# USB_UART.net
KiCad netlist of a schematic drawn in Altium Designer
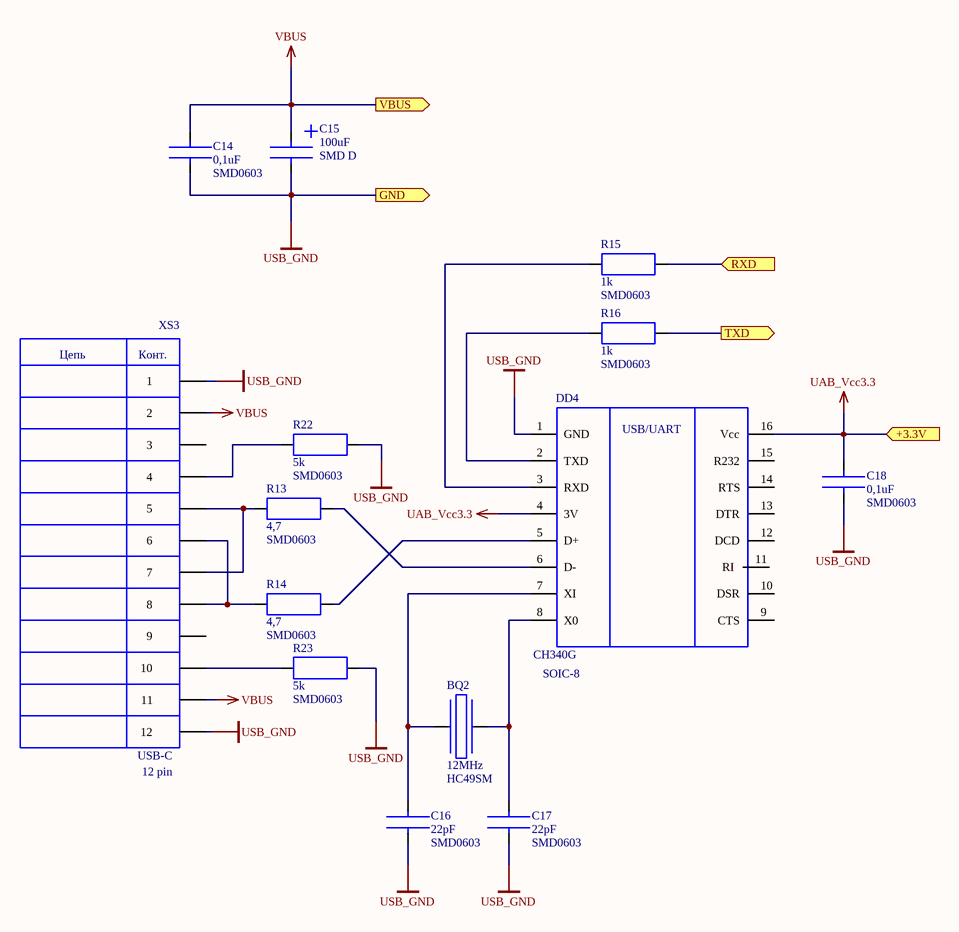
[diagram p0: USB_UART.SchDoc]

(export (version "E")
  (design (tool "Eeschema 10.0.6"))
  (components
    (comp (ref "BQ2")
      (value "12МHz")
      (footprint "BQ_HC49SM")
      (fields (field (name "PACKAGE") "HC49SM"))
      (libsource (lib "MechanikLibrary") (part "BQ_HC49SM"))
    )
    (comp (ref "C14")
      (value "0,1uF")
      (footprint "SMD0603(1005)")
      (fields (field (name "PACKAGE") "SMD0603"))
      (libsource (lib "MechanikLibrary") (part "CER_CUP_0603"))
    )
    (comp (ref "C15")
      (value "100uF")
      (footprint "TANT_CAP_D(7343)")
      (fields (field (name "PACKAGE") "SMD D"))
      (libsource (lib "MechanikLibrary") (part "C_TANT_D"))
    )
    (comp (ref "C16")
      (value "22pF")
      (footprint "SMD0603(1005)")
      (fields (field (name "PACKAGE") "SMD0603"))
      (libsource (lib "MechanikLibrary") (part "CER_CUP_0603"))
    )
    (comp (ref "C17")
      (value "22pF")
      (footprint "SMD0603(1005)")
      (fields (field (name "PACKAGE") "SMD0603"))
      (libsource (lib "MechanikLibrary") (part "CER_CUP_0603"))
    )
    (comp (ref "C18")
      (value "0,1uF")
      (footprint "SMD0603(1005)")
      (fields (field (name "PACKAGE") "SMD0603"))
      (libsource (lib "MechanikLibrary") (part "CER_CUP_0603"))
    )
    (comp (ref "DD4")
      (value "CH340G")
      (footprint "SOIC16")
      (fields (field (name "PACKAGE") "SOIC-8"))
      (libsource (lib "MechanikLibrary") (part "Микросхема CH340G"))
    )
    (comp (ref "R13")
      (value "4,7")
      (footprint "SMD0603(1005)")
      (fields (field (name "PACKAGE") "SMD0603"))
      (libsource (lib "MechanikLibrary") (part "R_0603"))
    )
    (comp (ref "R14")
      (value "4,7")
      (footprint "SMD0603(1005)")
      (fields (field (name "PACKAGE") "SMD0603"))
      (libsource (lib "MechanikLibrary") (part "R_0603"))
    )
    (comp (ref "R15")
      (value "1k")
      (footprint "SMD0603(1005)")
      (fields (field (name "PACKAGE") "SMD0603"))
      (libsource (lib "MechanikLibrary") (part "R_0603"))
    )
    (comp (ref "R16")
      (value "1k")
      (footprint "SMD0603(1005)")
      (fields (field (name "PACKAGE") "SMD0603"))
      (libsource (lib "MechanikLibrary") (part "R_0603"))
    )
    (comp (ref "R22")
      (value "5k")
      (footprint "SMD0603(1005)")
      (fields (field (name "PACKAGE") "SMD0603"))
      (libsource (lib "MechanikLibrary") (part "R_0603"))
    )
    (comp (ref "R23")
      (value "5k")
      (footprint "SMD0603(1005)")
      (fields (field (name "PACKAGE") "SMD0603"))
      (libsource (lib "MechanikLibrary") (part "R_0603"))
    )
    (comp (ref "XS3")
      (value "USB-C")
      (footprint "USB_C")
      (fields (field (name "PACKAGE") "12 pin"))
      (libsource (lib "MechanikLibrary") (part "USB_C"))
    )
  )
  (nets
    (net (code "1") (name "/RXD") (class "Default") (node (ref "R15") (pin "1") (pintype "passive")))
    (net (code "2") (name "/TXD") (class "Default") (node (ref "R16") (pin "1") (pintype "passive")))
    (net (code "3") (name "Net-(DD4-D+)") (class "Default")
      (node (ref "DD4") (pin "5") (pinfunction "D+_5") (pintype "passive"))
      (node (ref "R14") (pin "2") (pintype "passive"))
    )
    (net (code "4") (name "Net-(DD4-D-)") (class "Default")
      (node (ref "DD4") (pin "6") (pinfunction "D-_6") (pintype "passive"))
      (node (ref "R13") (pin "2") (pintype "passive"))
    )
    (net (code "5") (name "Net-(DD4-RXD)") (class "Default")
      (node (ref "DD4") (pin "3") (pinfunction "RXD_3") (pintype "passive"))
      (node (ref "R15") (pin "2") (pintype "passive"))
    )
    (net (code "6") (name "Net-(DD4-TXD)") (class "Default")
      (node (ref "DD4") (pin "2") (pinfunction "TXD_2") (pintype "passive"))
      (node (ref "R16") (pin "2") (pintype "passive"))
    )
    (net (code "7") (name "Net-(DD4-X0)") (class "Default")
      (node (ref "BQ2") (pin "2") (pintype "passive"))
      (node (ref "C17") (pin "2") (pintype "passive"))
      (node (ref "DD4") (pin "8") (pinfunction "X0_8") (pintype "passive"))
    )
    (net (code "8") (name "Net-(DD4-XI)") (class "Default")
      (node (ref "BQ2") (pin "1") (pintype "passive"))
      (node (ref "C16") (pin "2") (pintype "passive"))
      (node (ref "DD4") (pin "7") (pinfunction "XI_7") (pintype "passive"))
    )
    (net (code "9") (name "Net-(R13-Pad1)") (class "Default")
      (node (ref "R13") (pin "1") (pintype "passive"))
      (node (ref "XS3") (pin "5") (pinfunction "5_5") (pintype "passive"))
      (node (ref "XS3") (pin "7") (pinfunction "7_7") (pintype "passive"))
    )
    (net (code "10") (name "Net-(R14-Pad1)") (class "Default")
      (node (ref "R14") (pin "1") (pintype "passive"))
      (node (ref "XS3") (pin "6") (pinfunction "6_6") (pintype "passive"))
      (node (ref "XS3") (pin "8") (pinfunction "8_8") (pintype "passive"))
    )
    (net (code "11") (name "Net-(R22-Pad2)") (class "Default")
      (node (ref "R22") (pin "2") (pintype "passive"))
      (node (ref "XS3") (pin "4") (pinfunction "4_4") (pintype "passive"))
    )
    (net (code "12") (name "Net-(R23-Pad2)") (class "Default")
      (node (ref "R23") (pin "2") (pintype "passive"))
      (node (ref "XS3") (pin "10") (pinfunction "10_10") (pintype "passive"))
    )
    (net (code "13") (name "UAB_Vcc3.3") (class "Default")
      (node (ref "C18") (pin "2") (pintype "passive"))
      (node (ref "DD4") (pin "16") (pinfunction "Vcc_16") (pintype "passive"))
      (node (ref "DD4") (pin "4") (pinfunction "3V_4") (pintype "passive"))
    )
    (net (code "14") (name "USB_GND") (class "Default")
      (node (ref "C14") (pin "1") (pintype "passive"))
      (node (ref "C15") (pin "2") (pintype "passive"))
      (node (ref "C16") (pin "1") (pintype "passive"))
      (node (ref "C17") (pin "1") (pintype "passive"))
      (node (ref "C18") (pin "1") (pintype "passive"))
      (node (ref "DD4") (pin "1") (pinfunction "GND_1") (pintype "passive"))
      (node (ref "R22") (pin "1") (pintype "passive"))
      (node (ref "R23") (pin "1") (pintype "passive"))
      (node (ref "XS3") (pin "1") (pinfunction "1_1") (pintype "passive"))
      (node (ref "XS3") (pin "12") (pinfunction "12_12") (pintype "passive"))
    )
    (net (code "15") (name "VBUS") (class "Default")
      (node (ref "C14") (pin "2") (pintype "passive"))
      (node (ref "C15") (pin "1") (pintype "passive"))
      (node (ref "XS3") (pin "11") (pinfunction "11_11") (pintype "passive"))
      (node (ref "XS3") (pin "2") (pinfunction "2_2") (pintype "passive"))
    )
    (net (code "16") (name "unconnected-(DD4-CTS-Pad9)") (class "Default")
      (node (ref "DD4") (pin "9") (pinfunction "CTS_9") (pintype "passive"))
    )
    (net (code "17") (name "unconnected-(DD4-DCD-Pad12)") (class "Default")
      (node (ref "DD4") (pin "12") (pinfunction "DCD_12") (pintype "passive"))
    )
    (net (code "18") (name "unconnected-(DD4-DSR-Pad10)") (class "Default")
      (node (ref "DD4") (pin "10") (pinfunction "DSR_10") (pintype "passive"))
    )
    (net (code "19") (name "unconnected-(DD4-DTR-Pad13)") (class "Default")
      (node (ref "DD4") (pin "13") (pinfunction "DTR_13") (pintype "passive"))
    )
    (net (code "20") (name "unconnected-(DD4-R232-Pad15)") (class "Default")
      (node (ref "DD4") (pin "15") (pinfunction "R232_15") (pintype "passive"))
    )
    (net (code "21") (name "unconnected-(DD4-RI-Pad11)") (class "Default")
      (node (ref "DD4") (pin "11") (pinfunction "RI_11") (pintype "passive"))
    )
    (net (code "22") (name "unconnected-(DD4-RTS-Pad14)") (class "Default")
      (node (ref "DD4") (pin "14") (pinfunction "RTS_14") (pintype "passive"))
    )
    (net (code "23") (name "unconnected-(XS3-Pad3)") (class "Default")
      (node (ref "XS3") (pin "3") (pinfunction "3_3") (pintype "passive"))
    )
    (net (code "24") (name "unconnected-(XS3-Pad9)") (class "Default")
      (node (ref "XS3") (pin "9") (pinfunction "9_9") (pintype "passive"))
    )
  )
)
